# BeamBreakFix.net
KiCad netlist of a schematic drawn in Altium Designer
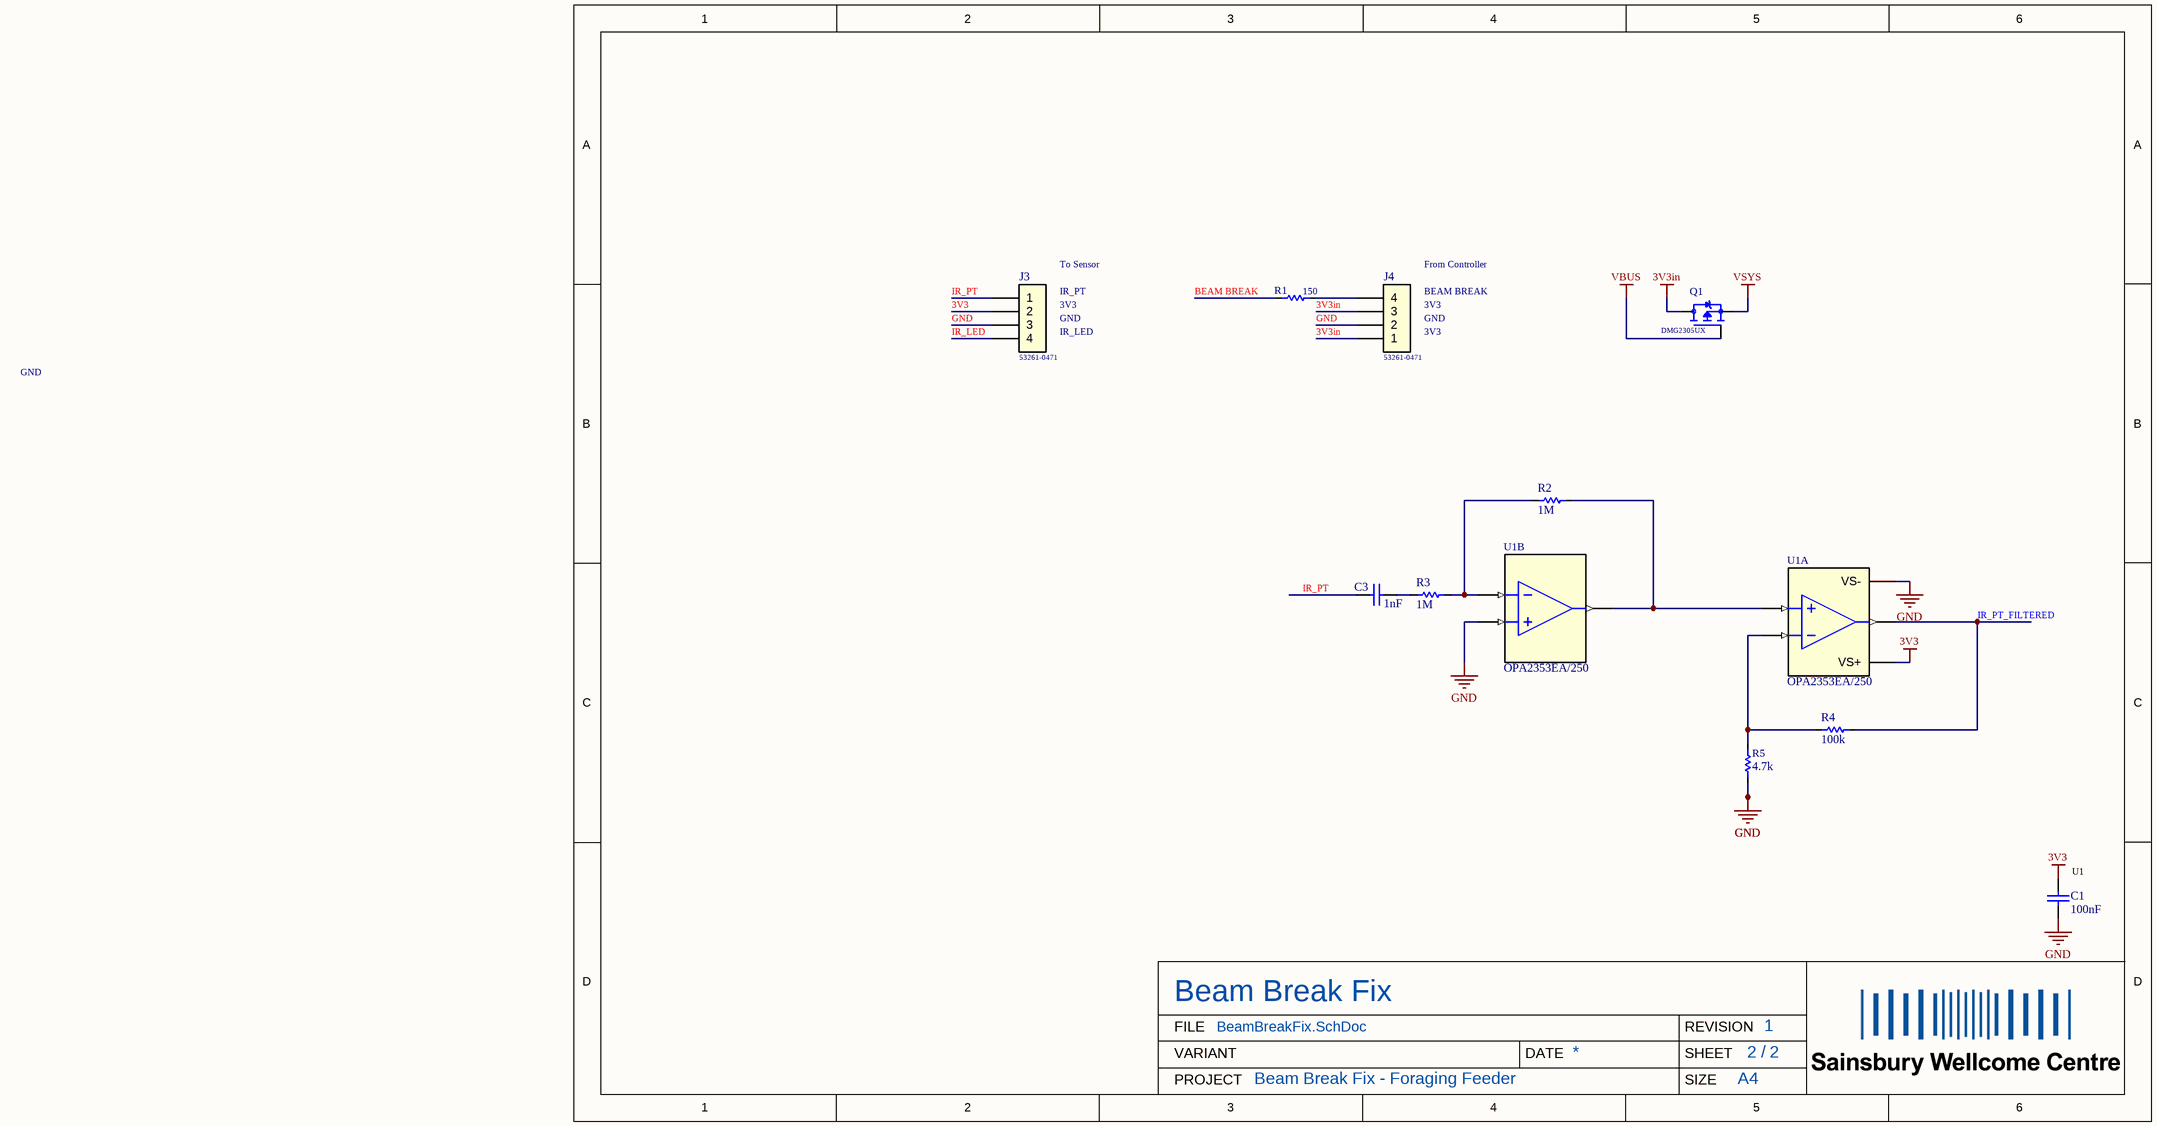
[diagram p0: BeamBreakFix.SchDoc]

(export (version "E")
  (design (tool "Eeschema 10.0.6"))
  (components
    (comp (ref "C1")
      (value "100nF")
      (footprint "FP-GRM188-0_1-e0_2_0_5-IPC_B")
      (description "0.1µF ±10% 100V Ceramic Capacitor X7R 0603 (1608 Metric)")
      (fields (field (name "VOLTAGE") "100V") (field (name "TOLERANCE") "10%"))
      (libsource (lib "Sainsbury Wellcome Centre") (part "Cap"))
    )
    (comp (ref "C3")
      (value "1nF")
      (footprint "FP-0603-L_1_6_0_15-W_0_81-IPC_C")
      (description "0.001µF ±1% 50V Ceramic Capacitor C0G 0603 (1608 Metric)")
      (fields (field (name "TOLERANCE") "1%") (field (name "PARTNUMBER") "C0603-1nF-50V-5%-COG"))
      (libsource (lib "Sainsbury Wellcome Centre") (part "Cap"))
    )
    (comp (ref "J3")
      (value "53261-0471")
      (footprint "MOLEX_53261-0471")
      (description "MOLEX 1.25mm (.049\") Pitch PicoBlade Header, Surface Mount, Right Angle, Lead-free, 4 Circuits")
      (libsource (lib "") (part "Jack 4x1_1"))
    )
    (comp (ref "J4")
      (value "53261-0471")
      (footprint "MOLEX_53261-0471")
      (description "MOLEX 1.25mm (.049\") Pitch PicoBlade Header, Surface Mount, Right Angle, Lead-free, 4 Circuits")
      (libsource (lib "Sainsbury Wellcome Centre") (part "Jack 4x1"))
    )
    (comp (ref "Q1")
      (value "DMG2305UX-7")
      (footprint "FP-SOT23-IPC_B")
      (fields (field (name "PARTNUMBER") "DMG2305UX"))
      (libsource (lib "Sainsbury Wellcome Centre") (part "87831b450059b469d4a68f5364f4496"))
    )
    (comp (ref "R1")
      (value "150")
      (footprint "FP-CPF0603-IPC_B")
      (description "Surface Mount Resistor 150 Ohm 1/16 W 0.1% 0603 (1608 Metric)")
      (fields (field (name "TOLERANCE") "0.1%") (field (name "Comment") "R0603-150R-1/16W-0.1%"))
      (libsource (lib "Sainsbury Wellcome Centre") (part "Res"))
    )
    (comp (ref "R2")
      (value "1M")
      (footprint "FP-CPF0603-IPC_B")
      (description "Surface Mount Resistor 1M Ohm 1/16 W 0.1% 0603 (1608 Metric)")
      (fields (field (name "TOLERANCE") "0.1%") (field (name "Comment") "R0603-1M-1/16W-0.1%"))
      (libsource (lib "Sainsbury Wellcome Centre") (part "Res"))
    )
    (comp (ref "R3")
      (value "1M")
      (footprint "FP-CPF0603-IPC_B")
      (description "Surface Mount Resistor 1M Ohm 1/16 W 0.1% 0603 (1608 Metric)")
      (fields (field (name "TOLERANCE") "0.1%") (field (name "Comment") "R0603-1M-1/16W-0.1%"))
      (libsource (lib "Sainsbury Wellcome Centre") (part "Res"))
    )
    (comp (ref "R4")
      (value "100k")
      (footprint "FP-CPF0603-IPC_B")
      (description "Surface Mount Resistor 100k Ohm 1/16 W 0.1% 0603 (1608 Metric)")
      (fields (field (name "TOLERANCE") "0.1%") (field (name "Comment") "R0603-100k-1/16W-0.1%"))
      (libsource (lib "Sainsbury Wellcome Centre") (part "Res"))
    )
    (comp (ref "R5")
      (value "4.7k")
      (footprint "FP-CPF0603-IPC_B")
      (description "Surface Mount Resistor 4.7k Ohm 1/16 W 0.1% 0603 (1608 Metric)")
      (fields (field (name "TOLERANCE") "0.1%") (field (name "Comment") "R0603-4k7-1/16W-0.1%"))
      (libsource (lib "Sainsbury Wellcome Centre") (part "Res"))
    )
    (comp (ref "U1")
      (value "OPA2353EA/250")
      (footprint "DGK0008A_N")
      (description "Operational Amplifier, 2 Func, 8000uV Offset-Max, CMOS, PDSO8")
      (fields (field (name "PARTNUMBER") "OPA2353EA/250"))
      (libsource (lib "") (part "TI-OPA-8_2_1"))
    )
  )
  (nets
    (net (code "1") (name "/BEAM BREAK") (class "Default")
      (node (ref "R1") (pin "1") (pinfunction "1_1") (pintype "passive"))
    )
    (net (code "2") (name "/IR_LED") (class "Default")
      (node (ref "J3") (pin "4") (pinfunction "4_4") (pintype "passive"))
    )
    (net (code "3") (name "/IR_PT") (class "Default")
      (node (ref "C3") (pin "1") (pinfunction "1_1") (pintype "passive"))
      (node (ref "J3") (pin "1") (pinfunction "1_1") (pintype "passive"))
    )
    (net (code "4") (name "/IR_PT_FILTERED") (class "Default")
      (node (ref "R4") (pin "2") (pinfunction "2_2") (pintype "passive"))
      (node (ref "U1") (pin "1") (pinfunction "OUT_1") (pintype "output"))
    )
    (net (code "5") (name "3V3") (class "Default")
      (node (ref "C1") (pin "2") (pinfunction "2_2") (pintype "passive"))
      (node (ref "J3") (pin "2") (pinfunction "2_2") (pintype "passive"))
      (node (ref "U1") (pin "8") (pinfunction "VS+_8") (pintype "power_in"))
    )
    (net (code "6") (name "3V3in") (class "Default")
      (node (ref "J4") (pin "1") (pinfunction "1_1") (pintype "passive"))
      (node (ref "J4") (pin "3") (pinfunction "3_3") (pintype "passive"))
      (node (ref "Q1") (pin "3") (pinfunction "DRAIN_3") (pintype "passive"))
    )
    (net (code "7") (name "GND") (class "Default")
      (node (ref "C1") (pin "1") (pinfunction "1_1") (pintype "passive"))
      (node (ref "J3") (pin "3") (pinfunction "3_3") (pintype "passive"))
      (node (ref "J4") (pin "2") (pinfunction "2_2") (pintype "passive"))
      (node (ref "R5") (pin "1") (pinfunction "1_1") (pintype "passive"))
      (node (ref "U1") (pin "4") (pinfunction "VS-_4") (pintype "power_in"))
      (node (ref "U1") (pin "5") (pinfunction "IN+_5") (pintype "input"))
    )
    (net (code "8") (name "Net-(C3-Pad2)") (class "Default")
      (node (ref "C3") (pin "2") (pinfunction "2_2") (pintype "passive"))
      (node (ref "R3") (pin "1") (pinfunction "1_1") (pintype "passive"))
    )
    (net (code "9") (name "Net-(J4-Pad4)") (class "Default")
      (node (ref "J4") (pin "4") (pinfunction "4_4") (pintype "passive"))
      (node (ref "R1") (pin "2") (pinfunction "2_2") (pintype "passive"))
    )
    (net (code "10") (name "Net-(U1A-IN+)") (class "Default")
      (node (ref "R2") (pin "2") (pinfunction "2_2") (pintype "passive"))
      (node (ref "U1") (pin "3") (pinfunction "IN+_3") (pintype "input"))
      (node (ref "U1") (pin "7") (pinfunction "OUT_7") (pintype "output"))
    )
    (net (code "11") (name "Net-(U1A-IN-)") (class "Default")
      (node (ref "R4") (pin "1") (pinfunction "1_1") (pintype "passive"))
      (node (ref "R5") (pin "2") (pinfunction "2_2") (pintype "passive"))
      (node (ref "U1") (pin "2") (pinfunction "IN-_2") (pintype "input"))
    )
    (net (code "12") (name "Net-(U1B-IN-)") (class "Default")
      (node (ref "R2") (pin "1") (pinfunction "1_1") (pintype "passive"))
      (node (ref "R3") (pin "2") (pinfunction "2_2") (pintype "passive"))
      (node (ref "U1") (pin "6") (pinfunction "IN-_6") (pintype "input"))
    )
    (net (code "13") (name "VBUS") (class "Default")
      (node (ref "Q1") (pin "1") (pinfunction "GATE_1") (pintype "passive"))
    )
    (net (code "14") (name "VSYS") (class "Default")
      (node (ref "Q1") (pin "2") (pinfunction "SOURCE_2") (pintype "passive"))
    )
  )
)
